# BRAINS.net
KiCad netlist of a schematic drawn in Altium Designer
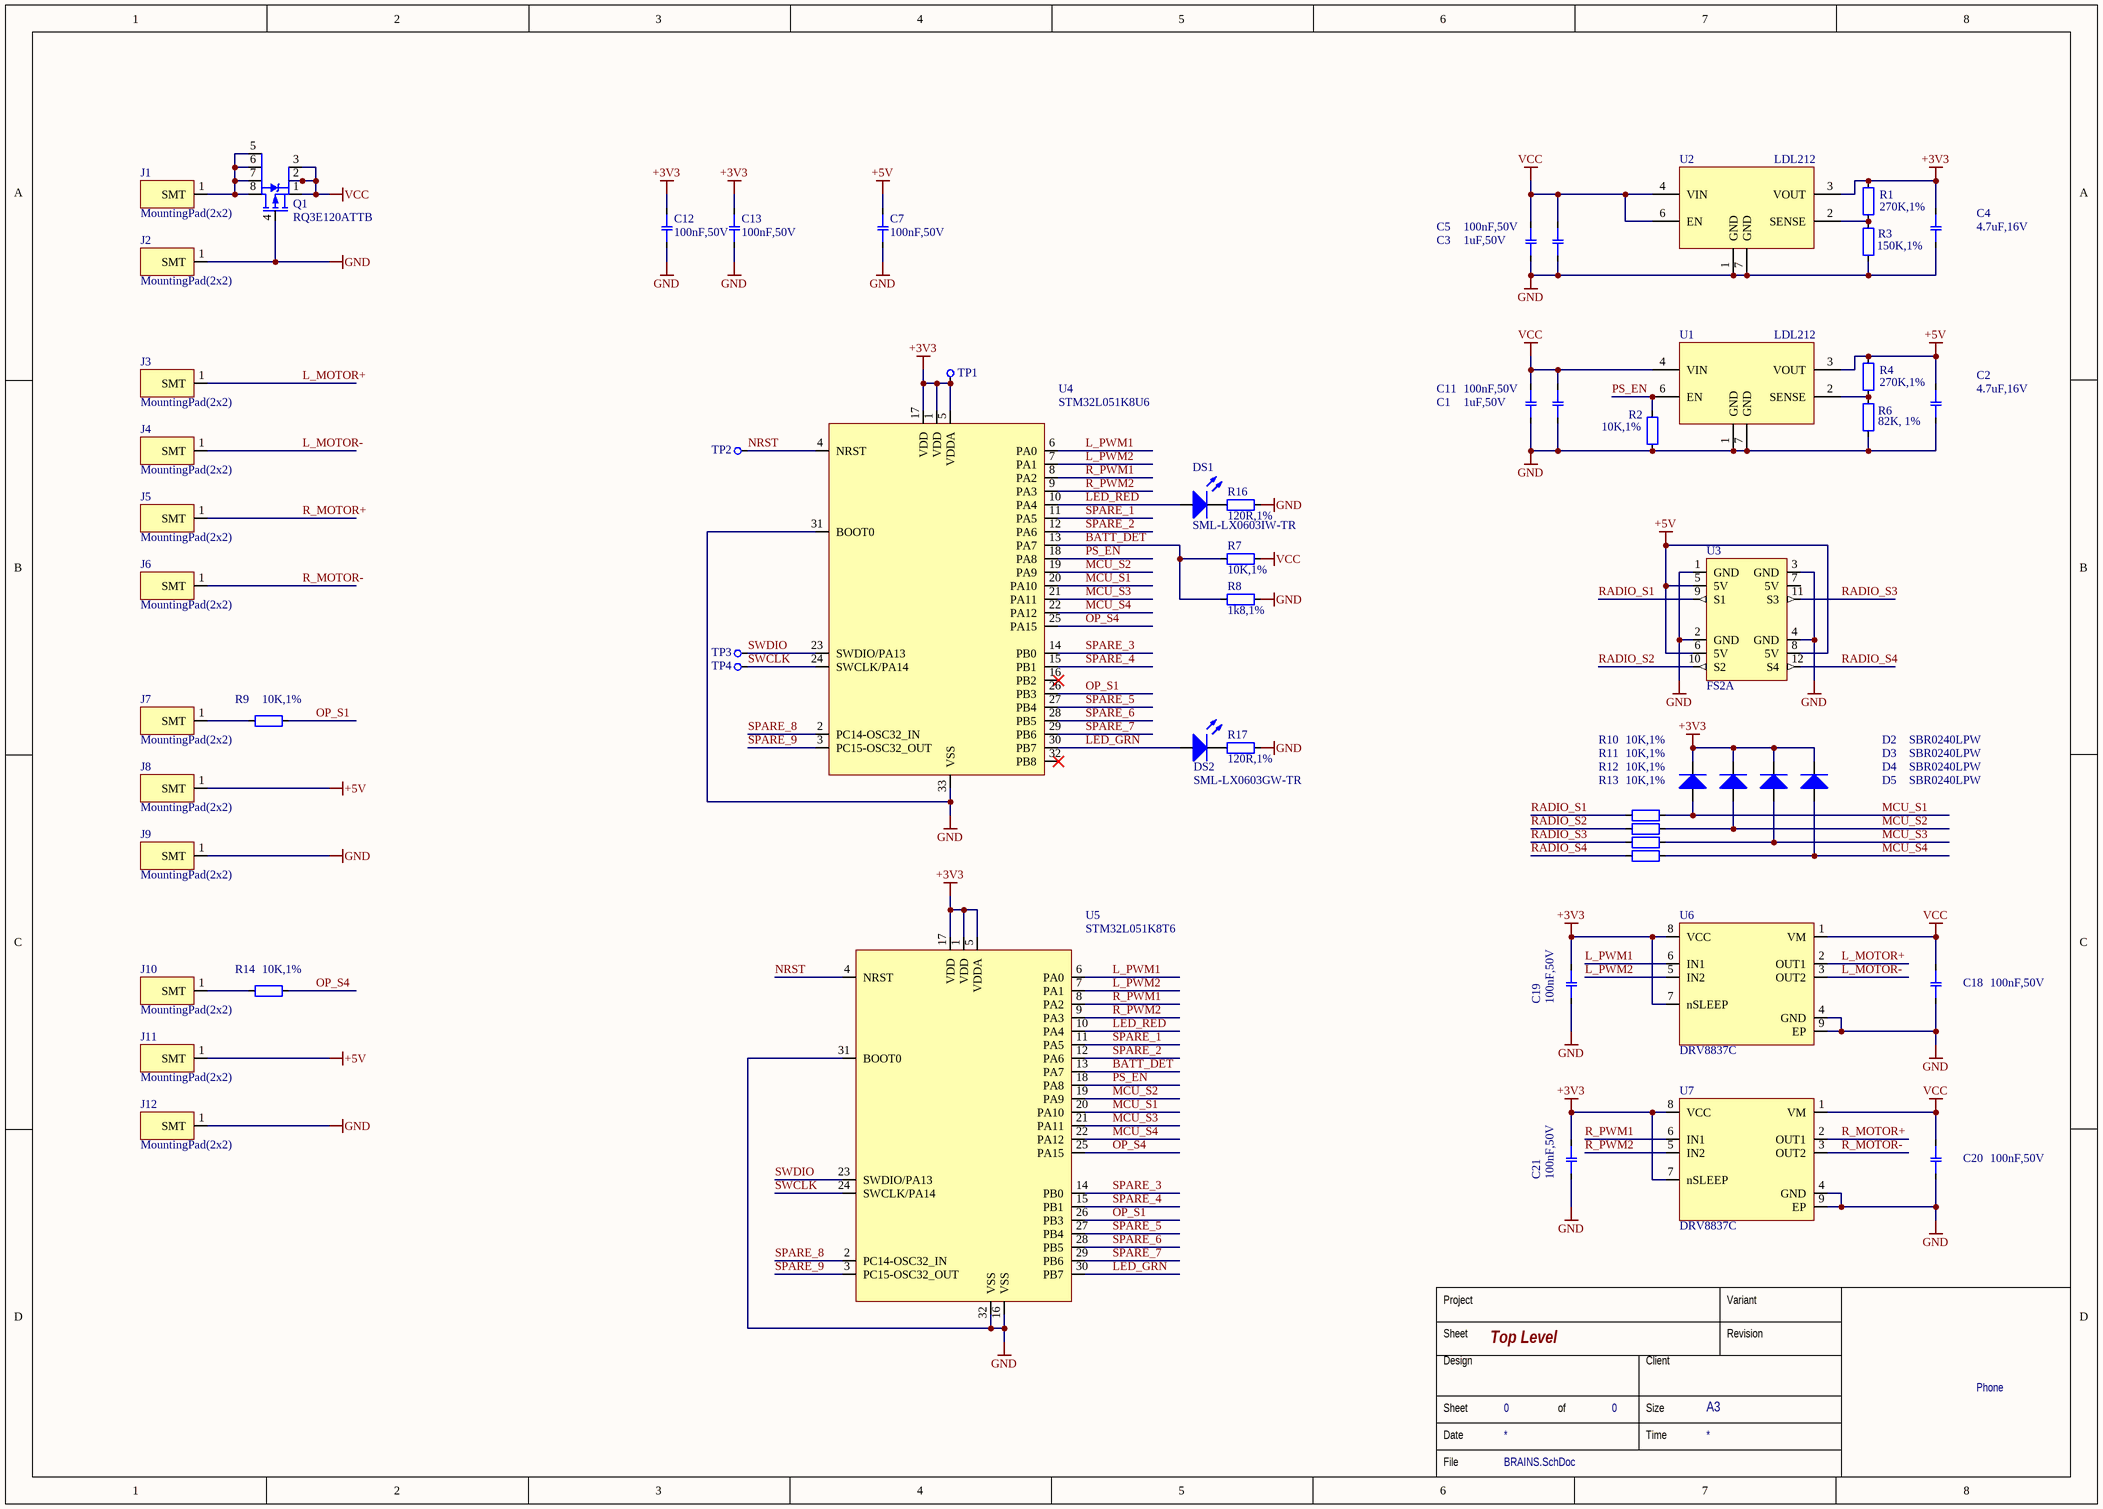
[diagram p0: BRAINS.SchDoc]

(export (version "E")
  (design (tool "Eeschema 10.0.6"))
  (components
    (comp (ref "C1")
      (value "1uF,50V")
      (footprint "CAPC1005X05N_0402")
      (description "CAP CER 1UF 50V X5R 0402")
      (fields (field (name "MANUFACTURER") "Taiyo Yuden") (field (name "TOLERANCE") "20%"))
      (libsource (lib "library") (part "CAP-NP_1"))
    )
    (comp (ref "C2")
      (value "4.7uF,16V")
      (footprint "CAPC1005X05N_0402")
      (description "CAP CER 4.7UF 16V X5R 0402")
      (fields (field (name "MANUFACTURER") "AVX Corporation") (field (name "TOLERANCE") "20%"))
      (libsource (lib "library") (part "CAP-NP_1"))
    )
    (comp (ref "C3")
      (value "1uF,50V")
      (footprint "CAPC1005X05N_0402")
      (description "CAP CER 1UF 50V X5R 0402")
      (fields (field (name "MANUFACTURER") "Taiyo Yuden") (field (name "TOLERANCE") "20%"))
      (libsource (lib "library") (part "CAP-NP_1"))
    )
    (comp (ref "C4")
      (value "4.7uF,16V")
      (footprint "CAPC1005X05N_0402")
      (description "CAP CER 4.7UF 16V X5R 0402")
      (fields (field (name "MANUFACTURER") "AVX Corporation") (field (name "TOLERANCE") "20%"))
      (libsource (lib "library") (part "CAP-NP_1"))
    )
    (comp (ref "C5")
      (value "100nF,50V")
      (footprint "CAPC1005X05N_0402")
      (description "CAP CER 100nF 50V X7R 0402")
      (fields (field (name "MANUFACTURER") "Taiyo Yuden") (field (name "TOLERANCE") "10%"))
      (libsource (lib "library") (part "CAP-NP_1"))
    )
    (comp (ref "C7")
      (value "100nF,50V")
      (footprint "CAPC1005X05N_0402")
      (description "CAP CER 100nF 50V X7R 0402")
      (fields (field (name "MANUFACTURER") "Taiyo Yuden") (field (name "TOLERANCE") "10%"))
      (libsource (lib "library") (part "CAP-NP_1"))
    )
    (comp (ref "C11")
      (value "100nF,50V")
      (footprint "CAPC1005X05N_0402")
      (description "CAP CER 100nF 50V X7R 0402")
      (fields (field (name "MANUFACTURER") "Taiyo Yuden") (field (name "TOLERANCE") "10%"))
      (libsource (lib "library") (part "CAP-NP_1"))
    )
    (comp (ref "C12")
      (value "100nF,50V")
      (footprint "CAPC1005X05N_0402")
      (description "CAP CER 100nF 50V X7R 0402")
      (fields (field (name "MANUFACTURER") "Taiyo Yuden") (field (name "TOLERANCE") "10%"))
      (libsource (lib "library") (part "CAP-NP_1"))
    )
    (comp (ref "C13")
      (value "100nF,50V")
      (footprint "CAPC1005X05N_0402")
      (description "CAP CER 100nF 50V X7R 0402")
      (fields (field (name "MANUFACTURER") "Taiyo Yuden") (field (name "TOLERANCE") "10%"))
      (libsource (lib "library") (part "CAP-NP_1"))
    )
    (comp (ref "C18")
      (value "100nF,50V")
      (footprint "CAPC1005X05N_0402")
      (description "CAP CER 100nF 50V X7R 0402")
      (fields (field (name "MANUFACTURER") "Taiyo Yuden") (field (name "TOLERANCE") "10%"))
      (libsource (lib "library") (part "CAP-NP_1"))
    )
    (comp (ref "C19")
      (value "100nF,50V")
      (footprint "CAPC1005X05N_0402")
      (description "CAP CER 100nF 50V X7R 0402")
      (fields (field (name "MANUFACTURER") "Taiyo Yuden") (field (name "TOLERANCE") "10%"))
      (libsource (lib "library") (part "CAP-NP_1"))
    )
    (comp (ref "C20")
      (value "100nF,50V")
      (footprint "CAPC1005X05N_0402")
      (description "CAP CER 100nF 50V X7R 0402")
      (fields (field (name "MANUFACTURER") "Taiyo Yuden") (field (name "TOLERANCE") "10%"))
      (libsource (lib "library") (part "CAP-NP_1"))
    )
    (comp (ref "C21")
      (value "100nF,50V")
      (footprint "CAPC1005X05N_0402")
      (description "CAP CER 100nF 50V X7R 0402")
      (fields (field (name "MANUFACTURER") "Taiyo Yuden") (field (name "TOLERANCE") "10%"))
      (libsource (lib "library") (part "CAP-NP_1"))
    )
    (comp (ref "D2")
      (value "SBR0240LPW")
      (footprint "TVS0402")
      (description "SBR DIODE X1-DFN1006-2/SWP")
      (fields
        (field (name "MANUFACTURER") "Diodes Incorporated")
        (field (name "MANUFACTURER PART NUMBER") "SBR0240LPW-7B")
      )
      (libsource (lib "library") (part "DIODE_1"))
    )
    (comp (ref "D3")
      (value "SBR0240LPW")
      (footprint "TVS0402")
      (description "SBR DIODE X1-DFN1006-2/SWP")
      (fields
        (field (name "MANUFACTURER") "Diodes Incorporated")
        (field (name "MANUFACTURER PART NUMBER") "SBR0240LPW-7B")
      )
      (libsource (lib "library") (part "DIODE_1"))
    )
    (comp (ref "D4")
      (value "SBR0240LPW")
      (footprint "TVS0402")
      (description "SBR DIODE X1-DFN1006-2/SWP")
      (fields
        (field (name "MANUFACTURER") "Diodes Incorporated")
        (field (name "MANUFACTURER PART NUMBER") "SBR0240LPW-7B")
      )
      (libsource (lib "library") (part "DIODE_1"))
    )
    (comp (ref "D5")
      (value "SBR0240LPW")
      (footprint "TVS0402")
      (description "SBR DIODE X1-DFN1006-2/SWP")
      (fields
        (field (name "MANUFACTURER") "Diodes Incorporated")
        (field (name "MANUFACTURER PART NUMBER") "SBR0240LPW-7B")
      )
      (libsource (lib "library") (part "DIODE_1"))
    )
    (comp (ref "DS1")
      (value "SML-LX0603IW-TR")
      (footprint "LED_SML-LX0603")
      (description "LED 635NM RED DIFF 0603 SMD")
      (fields (field (name "MANUFACTURER") "Lumex Opto/Components Inc"))
      (libsource (lib "library") (part "LED_1"))
    )
    (comp (ref "DS2")
      (value "SML-LX0603GW-TR")
      (footprint "LED_SML-LX0603")
      (description "LED 565NM GRN DIFF 0603 SMD")
      (fields (field (name "MANUFACTURER") "Lumex Opto/Components Inc"))
      (libsource (lib "library") (part "LED_1"))
    )
    (comp (ref "J1")
      (value "MountingPad(2x2)")
      (footprint "MountingPad(2x2)")
      (libsource (lib "") (part "MountingPad(2x2)_1"))
    )
    (comp (ref "J2")
      (value "MountingPad(2x2)")
      (footprint "MountingPad(2x2)")
      (libsource (lib "") (part "MountingPad(2x2)_1"))
    )
    (comp (ref "J3")
      (value "MountingPad(2x2)")
      (footprint "MountingPad(2x2)")
      (libsource (lib "Schlib1") (part "MountingPad(2x2)"))
    )
    (comp (ref "J4")
      (value "MountingPad(2x2)")
      (footprint "MountingPad(2x2)")
      (libsource (lib "Schlib1") (part "MountingPad(2x2)"))
    )
    (comp (ref "J5")
      (value "MountingPad(2x2)")
      (footprint "MountingPad(2x2)")
      (libsource (lib "Schlib1") (part "MountingPad(2x2)"))
    )
    (comp (ref "J6")
      (value "MountingPad(2x2)")
      (footprint "MountingPad(2x2)")
      (libsource (lib "Schlib1") (part "MountingPad(2x2)"))
    )
    (comp (ref "J7")
      (value "MountingPad(2x2)")
      (footprint "MountingPad(2x2)")
      (libsource (lib "Schlib1") (part "MountingPad(2x2)"))
    )
    (comp (ref "J8")
      (value "MountingPad(2x2)")
      (footprint "MountingPad(2x2)")
      (libsource (lib "Schlib1") (part "MountingPad(2x2)"))
    )
    (comp (ref "J9")
      (value "MountingPad(2x2)")
      (footprint "MountingPad(2x2)")
      (libsource (lib "Schlib1") (part "MountingPad(2x2)"))
    )
    (comp (ref "J10")
      (value "MountingPad(2x2)")
      (footprint "MountingPad(2x2)")
      (libsource (lib "Schlib1") (part "MountingPad(2x2)"))
    )
    (comp (ref "J11")
      (value "MountingPad(2x2)")
      (footprint "MountingPad(2x2)")
      (libsource (lib "Schlib1") (part "MountingPad(2x2)"))
    )
    (comp (ref "J12")
      (value "MountingPad(2x2)")
      (footprint "MountingPad(2x2)")
      (libsource (lib "Schlib1") (part "MountingPad(2x2)"))
    )
    (comp (ref "Q1")
      (value "RQ3E120ATTB")
      (footprint "ROHM-HSMT8")
      (description "MOSFET P-CH 30V 12A 8HSMT")
      (fields (field (name "MANUFACTURER") "Rohm Semiconductor"))
      (libsource (lib "library") (part "MOSFET-P_5"))
    )
    (comp (ref "R1")
      (value "270K,1%")
      (footprint "RESC1005X04N_0402")
      (description "RES SMD 270K OHM 1% 1/16W 0402")
      (fields (field (name "MANUFACTURER") "Yageo") (field (name "POWER") "0.063W"))
      (libsource (lib "library") (part "RESISTOR_1"))
    )
    (comp (ref "R2")
      (value "10K,1%")
      (footprint "RESC1005X04N_0402")
      (description "RES 10K OHM 1/16W 1% 0402 SMD")
      (fields (field (name "MANUFACTURER") "Yageo") (field (name "POWER") "0.0625W"))
      (libsource (lib "library") (part "RESISTOR_1"))
    )
    (comp (ref "R3")
      (value "150K,1%")
      (footprint "RESC1005X04N_0402")
      (description "RES SMD 150K OHM 1% 1/16W 0402")
      (fields (field (name "MANUFACTURER") "Yageo") (field (name "POWER") "0.063W"))
      (libsource (lib "library") (part "RESISTOR_1"))
    )
    (comp (ref "R4")
      (value "270K,1%")
      (footprint "RESC1005X04N_0402")
      (description "RES SMD 270K OHM 1% 1/16W 0402")
      (fields (field (name "MANUFACTURER") "Yageo") (field (name "POWER") "0.063W"))
      (libsource (lib "library") (part "RESISTOR_1"))
    )
    (comp (ref "R6")
      (value "82K, 1%")
      (footprint "RESC1005X04N_0402")
      (description "RES SMD 82K OHM 1% 1/16W 0402")
      (fields (field (name "MANUFACTURER") "YAGEO") (field (name "POWER") "0.063W"))
      (libsource (lib "library") (part "RESISTOR_1"))
    )
    (comp (ref "R7")
      (value "10K,1%")
      (footprint "RESC1005X04N_0402")
      (description "RES 10K OHM 1/16W 1% 0402 SMD")
      (fields (field (name "MANUFACTURER") "Yageo") (field (name "POWER") "0.0625W"))
      (libsource (lib "") (part "RESISTOR_1_2"))
    )
    (comp (ref "R8")
      (value "1k8,1%")
      (footprint "RESC1005X04N_0402")
      (description "RES 1k8 0.0625W 1% 0402 SMD")
      (fields (field (name "MANUFACTURER") "Vishay Dale") (field (name "POWER") "0.0625W"))
      (libsource (lib "") (part "RESISTOR_1_2"))
    )
    (comp (ref "R9")
      (value "10K,1%")
      (footprint "RESC1005X04N_0402")
      (description "RES 10K OHM 1/16W 1% 0402 SMD")
      (fields (field (name "MANUFACTURER") "Yageo") (field (name "POWER") "0.0625W"))
      (libsource (lib "") (part "RESISTOR_1_1"))
    )
    (comp (ref "R10")
      (value "10K,1%")
      (footprint "RESC1005X04N_0402")
      (description "RES 10K OHM 1/16W 1% 0402 SMD")
      (fields (field (name "MANUFACTURER") "Yageo") (field (name "POWER") "0.0625W"))
      (libsource (lib "") (part "RESISTOR_1_1"))
    )
    (comp (ref "R11")
      (value "10K,1%")
      (footprint "RESC1005X04N_0402")
      (description "RES 10K OHM 1/16W 1% 0402 SMD")
      (fields (field (name "MANUFACTURER") "Yageo") (field (name "POWER") "0.0625W"))
      (libsource (lib "") (part "RESISTOR_1_1"))
    )
    (comp (ref "R12")
      (value "10K,1%")
      (footprint "RESC1005X04N_0402")
      (description "RES 10K OHM 1/16W 1% 0402 SMD")
      (fields (field (name "MANUFACTURER") "Yageo") (field (name "POWER") "0.0625W"))
      (libsource (lib "") (part "RESISTOR_1_1"))
    )
    (comp (ref "R13")
      (value "10K,1%")
      (footprint "RESC1005X04N_0402")
      (description "RES 10K OHM 1/16W 1% 0402 SMD")
      (fields (field (name "MANUFACTURER") "Yageo") (field (name "POWER") "0.0625W"))
      (libsource (lib "") (part "RESISTOR_1_1"))
    )
    (comp (ref "R14")
      (value "10K,1%")
      (footprint "RESC1005X04N_0402")
      (description "RES 10K OHM 1/16W 1% 0402 SMD")
      (fields (field (name "MANUFACTURER") "Yageo") (field (name "POWER") "0.0625W"))
      (libsource (lib "") (part "RESISTOR_1_1"))
    )
    (comp (ref "R16")
      (value "120R,1%")
      (footprint "RESC1005X04N_0402")
      (description "RES 120 OHM 1/16W 0402 SMD")
      (fields (field (name "MANUFACTURER") "Yageo") (field (name "POWER") "0.0625W"))
      (libsource (lib "") (part "RESISTOR_1_2"))
    )
    (comp (ref "R17")
      (value "120R,1%")
      (footprint "RESC1005X04N_0402")
      (description "RES 120 OHM 1/16W 0402 SMD")
      (fields (field (name "MANUFACTURER") "Yageo") (field (name "POWER") "0.0625W"))
      (libsource (lib "") (part "RESISTOR_1_2"))
    )
    (comp (ref "TP1")
      (value "TP_SMT")
      (footprint "TP_050")
      (description "Test Point - SMT")
      (libsource (lib "library") (part "TP_1"))
    )
    (comp (ref "TP2")
      (value "TP_SMT")
      (footprint "TP_050")
      (description "Test Point - SMT")
      (libsource (lib "library") (part "TP_1"))
    )
    (comp (ref "TP3")
      (value "TP_SMT")
      (footprint "TP_050")
      (description "Test Point - SMT")
      (libsource (lib "library") (part "TP_1"))
    )
    (comp (ref "TP4")
      (value "TP_SMT")
      (footprint "TP_050")
      (description "Test Point - SMT")
      (libsource (lib "library") (part "TP_1"))
    )
    (comp (ref "U1")
      (value "LDL212")
      (footprint "DFN65P300X300X80-8N_PWSON6")
      (description "IC REG LINEAR 5V 1.2A 6DFN")
      (fields
        (field (name "MANUFACTURER") "STMicroelectronics")
        (field (name "MANUFACTURER PART NUMBER") "LDL212PU50R")
      )
      (libsource (lib "library") (part "LDL212PU50R"))
    )
    (comp (ref "U2")
      (value "LDL212")
      (footprint "DFN65P300X300X80-8N_PWSON6")
      (description "IC REG LINEAR 5V 1.2A 6DFN")
      (fields
        (field (name "MANUFACTURER") "STMicroelectronics")
        (field (name "MANUFACTURER PART NUMBER") "LDL212PU50R")
      )
      (libsource (lib "library") (part "LDL212PU50R"))
    )
    (comp (ref "U3") (value "FS2A") (footprint "FS2A") (libsource (lib "Schlib1") (part "FS2A")))
    (comp (ref "U4")
      (value "STM32L051K8U6")
      (footprint "QFN50P500X500X100-32N_32QFN_2")
      (description "IC MCU 32BIT 64KB FLASH 32UFQFPN")
      (fields (field (name "MANUFACTURER") "STMicroelectronics"))
      (libsource (lib "library") (part "STM32L051x6/8U"))
    )
    (comp (ref "U5")
      (value "STM32L051K8T6")
      (footprint "LQFP32")
      (description "32 Bit Mcirocontroler")
      (fields (field (name "MANUFACTURER") "ST Microelectronics"))
      (libsource (lib "library") (part "STM32L051x6/8"))
    )
    (comp (ref "U6")
      (value "DRV8837C")
      (footprint "DFN50P200X200X80-8N")
      (description "IC HALF-BRIDGE DRVR PWM 8WSON")
      (fields
        (field (name "MANUFACTURER") "Texas Instruments")
        (field (name "MANUFACTURER PART NUMBER") "DRV8837CDSGR")
      )
      (libsource (lib "library") (part "DRV8837C"))
    )
    (comp (ref "U7")
      (value "DRV8837C")
      (footprint "DFN50P200X200X80-8N")
      (description "IC HALF-BRIDGE DRVR PWM 8WSON")
      (fields
        (field (name "MANUFACTURER") "Texas Instruments")
        (field (name "MANUFACTURER PART NUMBER") "DRV8837CDSGR")
      )
      (libsource (lib "library") (part "DRV8837C"))
    )
  )
  (nets
    (net (code "1") (name "+3V3") (class "Default")
      (node (ref "C12") (pin "2") (pinfunction "2_2") (pintype "passive"))
      (node (ref "C13") (pin "2") (pinfunction "2_2") (pintype "passive"))
      (node (ref "C19") (pin "2") (pinfunction "2_2") (pintype "passive"))
      (node (ref "C21") (pin "2") (pinfunction "2_2") (pintype "passive"))
      (node (ref "C4") (pin "2") (pinfunction "2_2") (pintype "passive"))
      (node (ref "D2") (pin "1") (pinfunction "C_1") (pintype "passive"))
      (node (ref "D3") (pin "1") (pinfunction "C_1") (pintype "passive"))
      (node (ref "D4") (pin "1") (pinfunction "C_1") (pintype "passive"))
      (node (ref "D5") (pin "1") (pinfunction "C_1") (pintype "passive"))
      (node (ref "R1") (pin "2") (pinfunction "2_2") (pintype "passive"))
      (node (ref "TP1") (pin "1") (pinfunction "1_1") (pintype "passive"))
      (node (ref "U2") (pin "3") (pinfunction "VOUT_3") (pintype "passive"))
      (node (ref "U4") (pin "1") (pinfunction "VDD_1") (pintype "passive"))
      (node (ref "U4") (pin "17") (pinfunction "VDD_17") (pintype "passive"))
      (node (ref "U4") (pin "5") (pinfunction "VDDA_5") (pintype "passive"))
      (node (ref "U5") (pin "1") (pinfunction "VDD_1") (pintype "passive"))
      (node (ref "U5") (pin "17") (pinfunction "VDD_17") (pintype "passive"))
      (node (ref "U5") (pin "5") (pinfunction "VDDA_5") (pintype "passive"))
      (node (ref "U6") (pin "7") (pinfunction "nSLEEP_7") (pintype "passive"))
      (node (ref "U6") (pin "8") (pinfunction "VCC_8") (pintype "passive"))
      (node (ref "U7") (pin "7") (pinfunction "nSLEEP_7") (pintype "passive"))
      (node (ref "U7") (pin "8") (pinfunction "VCC_8") (pintype "passive"))
    )
    (net (code "2") (name "+5V") (class "Default")
      (node (ref "C2") (pin "2") (pinfunction "2_2") (pintype "passive"))
      (node (ref "C7") (pin "2") (pinfunction "2_2") (pintype "passive"))
      (node (ref "J11") (pin "1") (pinfunction "SMT_1") (pintype "passive"))
      (node (ref "J8") (pin "1") (pinfunction "SMT_1") (pintype "passive"))
      (node (ref "R4") (pin "2") (pinfunction "2_2") (pintype "passive"))
      (node (ref "U1") (pin "3") (pinfunction "VOUT_3") (pintype "passive"))
      (node (ref "U3") (pin "5") (pinfunction "5V_5") (pintype "power_in"))
      (node (ref "U3") (pin "6") (pinfunction "5V_6") (pintype "power_in"))
      (node (ref "U3") (pin "8") (pinfunction "5V_8") (pintype "power_in"))
    )
    (net (code "3") (name "/BATT_DET") (class "Default")
      (node (ref "R7") (pin "2") (pinfunction "2_2") (pintype "passive"))
      (node (ref "R8") (pin "2") (pinfunction "2_2") (pintype "passive"))
      (node (ref "U4") (pin "13") (pinfunction "PA7_13") (pintype "passive"))
      (node (ref "U5") (pin "13") (pinfunction "PA7_13") (pintype "passive"))
    )
    (net (code "4") (name "/LED_GRN") (class "Default")
      (node (ref "DS2") (pin "2") (pinfunction "A_2") (pintype "passive"))
      (node (ref "U4") (pin "30") (pinfunction "PB7_30") (pintype "passive"))
      (node (ref "U5") (pin "30") (pinfunction "PB7_30") (pintype "passive"))
    )
    (net (code "5") (name "/LED_RED") (class "Default")
      (node (ref "DS1") (pin "2") (pinfunction "A_2") (pintype "passive"))
      (node (ref "U4") (pin "10") (pinfunction "PA4_10") (pintype "passive"))
      (node (ref "U5") (pin "10") (pinfunction "PA4_10") (pintype "passive"))
    )
    (net (code "6") (name "/L_MOTOR+") (class "Default")
      (node (ref "J3") (pin "1") (pinfunction "SMT_1") (pintype "passive"))
      (node (ref "U6") (pin "2") (pinfunction "OUT1_2") (pintype "passive"))
    )
    (net (code "7") (name "/L_MOTOR-") (class "Default")
      (node (ref "J4") (pin "1") (pinfunction "SMT_1") (pintype "passive"))
      (node (ref "U6") (pin "3") (pinfunction "OUT2_3") (pintype "passive"))
    )
    (net (code "8") (name "/L_PWM1") (class "Default")
      (node (ref "U4") (pin "6") (pinfunction "PA0_6") (pintype "passive"))
      (node (ref "U5") (pin "6") (pinfunction "PA0_6") (pintype "passive"))
      (node (ref "U6") (pin "6") (pinfunction "IN1_6") (pintype "passive"))
    )
    (net (code "9") (name "/L_PWM2") (class "Default")
      (node (ref "U4") (pin "7") (pinfunction "PA1_7") (pintype "passive"))
      (node (ref "U5") (pin "7") (pinfunction "PA1_7") (pintype "passive"))
      (node (ref "U6") (pin "5") (pinfunction "IN2_5") (pintype "passive"))
    )
    (net (code "10") (name "/MCU_S1") (class "Default")
      (node (ref "D5") (pin "2") (pinfunction "A_2") (pintype "passive"))
      (node (ref "R10") (pin "1") (pinfunction "1_1") (pintype "passive"))
      (node (ref "U4") (pin "20") (pinfunction "PA10_20") (pintype "passive"))
      (node (ref "U5") (pin "20") (pinfunction "PA10_20") (pintype "passive"))
    )
    (net (code "11") (name "/MCU_S2") (class "Default")
      (node (ref "D4") (pin "2") (pinfunction "A_2") (pintype "passive"))
      (node (ref "R11") (pin "1") (pinfunction "1_1") (pintype "passive"))
      (node (ref "U4") (pin "19") (pinfunction "PA9_19") (pintype "passive"))
      (node (ref "U5") (pin "19") (pinfunction "PA9_19") (pintype "passive"))
    )
    (net (code "12") (name "/MCU_S3") (class "Default")
      (node (ref "D3") (pin "2") (pinfunction "A_2") (pintype "passive"))
      (node (ref "R12") (pin "1") (pinfunction "1_1") (pintype "passive"))
      (node (ref "U4") (pin "21") (pinfunction "PA11_21") (pintype "passive"))
      (node (ref "U5") (pin "21") (pinfunction "PA11_21") (pintype "passive"))
    )
    (net (code "13") (name "/MCU_S4") (class "Default")
      (node (ref "D2") (pin "2") (pinfunction "A_2") (pintype "passive"))
      (node (ref "R13") (pin "1") (pinfunction "1_1") (pintype "passive"))
      (node (ref "U4") (pin "22") (pinfunction "PA12_22") (pintype "passive"))
      (node (ref "U5") (pin "22") (pinfunction "PA12_22") (pintype "passive"))
    )
    (net (code "14") (name "/NRST") (class "Default")
      (node (ref "TP2") (pin "1") (pinfunction "1_1") (pintype "passive"))
      (node (ref "U4") (pin "4") (pinfunction "NRST_4") (pintype "passive"))
      (node (ref "U5") (pin "4") (pinfunction "NRST_4") (pintype "passive"))
    )
    (net (code "15") (name "/OP_S1") (class "Default")
      (node (ref "R9") (pin "1") (pinfunction "1_1") (pintype "passive"))
      (node (ref "U4") (pin "26") (pinfunction "PB3_26") (pintype "passive"))
      (node (ref "U5") (pin "26") (pinfunction "PB3_26") (pintype "passive"))
    )
    (net (code "16") (name "/OP_S4") (class "Default")
      (node (ref "R14") (pin "1") (pinfunction "1_1") (pintype "passive"))
      (node (ref "U4") (pin "25") (pinfunction "PA15_25") (pintype "passive"))
      (node (ref "U5") (pin "25") (pinfunction "PA15_25") (pintype "passive"))
    )
    (net (code "17") (name "/PS_EN") (class "Default")
      (node (ref "R2") (pin "2") (pinfunction "2_2") (pintype "passive"))
      (node (ref "U1") (pin "6") (pinfunction "EN_6") (pintype "passive"))
      (node (ref "U4") (pin "18") (pinfunction "PA8_18") (pintype "passive"))
      (node (ref "U5") (pin "18") (pinfunction "PA8_18") (pintype "passive"))
    )
    (net (code "18") (name "/RADIO_S1") (class "Default")
      (node (ref "R10") (pin "2") (pinfunction "2_2") (pintype "passive"))
      (node (ref "U3") (pin "9") (pinfunction "S1_9") (pintype "output"))
    )
    (net (code "19") (name "/RADIO_S2") (class "Default")
      (node (ref "R11") (pin "2") (pinfunction "2_2") (pintype "passive"))
      (node (ref "U3") (pin "10") (pinfunction "S2_10") (pintype "output"))
    )
    (net (code "20") (name "/RADIO_S3") (class "Default")
      (node (ref "R12") (pin "2") (pinfunction "2_2") (pintype "passive"))
      (node (ref "U3") (pin "11") (pinfunction "S3_11") (pintype "output"))
    )
    (net (code "21") (name "/RADIO_S4") (class "Default")
      (node (ref "R13") (pin "2") (pinfunction "2_2") (pintype "passive"))
      (node (ref "U3") (pin "12") (pinfunction "S4_12") (pintype "output"))
    )
    (net (code "22") (name "/R_MOTOR+") (class "Default")
      (node (ref "J5") (pin "1") (pinfunction "SMT_1") (pintype "passive"))
      (node (ref "U7") (pin "2") (pinfunction "OUT1_2") (pintype "passive"))
    )
    (net (code "23") (name "/R_MOTOR-") (class "Default")
      (node (ref "J6") (pin "1") (pinfunction "SMT_1") (pintype "passive"))
      (node (ref "U7") (pin "3") (pinfunction "OUT2_3") (pintype "passive"))
    )
    (net (code "24") (name "/R_PWM1") (class "Default")
      (node (ref "U4") (pin "8") (pinfunction "PA2_8") (pintype "passive"))
      (node (ref "U5") (pin "8") (pinfunction "PA2_8") (pintype "passive"))
      (node (ref "U7") (pin "6") (pinfunction "IN1_6") (pintype "passive"))
    )
    (net (code "25") (name "/R_PWM2") (class "Default")
      (node (ref "U4") (pin "9") (pinfunction "PA3_9") (pintype "passive"))
      (node (ref "U5") (pin "9") (pinfunction "PA3_9") (pintype "passive"))
      (node (ref "U7") (pin "5") (pinfunction "IN2_5") (pintype "passive"))
    )
    (net (code "26") (name "/SPARE_1") (class "Default")
      (node (ref "U4") (pin "11") (pinfunction "PA5_11") (pintype "passive"))
      (node (ref "U5") (pin "11") (pinfunction "PA5_11") (pintype "passive"))
    )
    (net (code "27") (name "/SPARE_2") (class "Default")
      (node (ref "U4") (pin "12") (pinfunction "PA6_12") (pintype "passive"))
      (node (ref "U5") (pin "12") (pinfunction "PA6_12") (pintype "passive"))
    )
    (net (code "28") (name "/SPARE_3") (class "Default")
      (node (ref "U4") (pin "14") (pinfunction "PB0_14") (pintype "passive"))
      (node (ref "U5") (pin "14") (pinfunction "PB0_14") (pintype "passive"))
    )
    (net (code "29") (name "/SPARE_4") (class "Default")
      (node (ref "U4") (pin "15") (pinfunction "PB1_15") (pintype "passive"))
      (node (ref "U5") (pin "15") (pinfunction "PB1_15") (pintype "passive"))
    )
    (net (code "30") (name "/SPARE_5") (class "Default")
      (node (ref "U4") (pin "27") (pinfunction "PB4_27") (pintype "passive"))
      (node (ref "U5") (pin "27") (pinfunction "PB4_27") (pintype "passive"))
    )
    (net (code "31") (name "/SPARE_6") (class "Default")
      (node (ref "U4") (pin "28") (pinfunction "PB5_28") (pintype "passive"))
      (node (ref "U5") (pin "28") (pinfunction "PB5_28") (pintype "passive"))
    )
    (net (code "32") (name "/SPARE_7") (class "Default")
      (node (ref "U4") (pin "29") (pinfunction "PB6_29") (pintype "passive"))
      (node (ref "U5") (pin "29") (pinfunction "PB6_29") (pintype "passive"))
    )
    (net (code "33") (name "/SPARE_8") (class "Default")
      (node (ref "U4") (pin "2") (pinfunction "PC14-OSC32_IN_2") (pintype "passive"))
      (node (ref "U5") (pin "2") (pinfunction "PC14-OSC32_IN_2") (pintype "passive"))
    )
    (net (code "34") (name "/SPARE_9") (class "Default")
      (node (ref "U4") (pin "3") (pinfunction "PC15-OSC32_OUT_3") (pintype "passive"))
      (node (ref "U5") (pin "3") (pinfunction "PC15-OSC32_OUT_3") (pintype "passive"))
    )
    (net (code "35") (name "/SWCLK") (class "Default")
      (node (ref "TP4") (pin "1") (pinfunction "1_1") (pintype "passive"))
      (node (ref "U4") (pin "24") (pinfunction "SWCLK/PA14_24") (pintype "passive"))
      (node (ref "U5") (pin "24") (pinfunction "SWCLK/PA14_24") (pintype "passive"))
    )
    (net (code "36") (name "/SWDIO") (class "Default")
      (node (ref "TP3") (pin "1") (pinfunction "1_1") (pintype "passive"))
      (node (ref "U4") (pin "23") (pinfunction "SWDIO/PA13_23") (pintype "passive"))
      (node (ref "U5") (pin "23") (pinfunction "SWDIO/PA13_23") (pintype "passive"))
    )
    (net (code "37") (name "GND") (class "Default")
      (node (ref "C1") (pin "1") (pinfunction "1_1") (pintype "passive"))
      (node (ref "C11") (pin "1") (pinfunction "1_1") (pintype "passive"))
      (node (ref "C12") (pin "1") (pinfunction "1_1") (pintype "passive"))
      (node (ref "C13") (pin "1") (pinfunction "1_1") (pintype "passive"))
      (node (ref "C18") (pin "1") (pinfunction "1_1") (pintype "passive"))
      (node (ref "C19") (pin "1") (pinfunction "1_1") (pintype "passive"))
      (node (ref "C2") (pin "1") (pinfunction "1_1") (pintype "passive"))
      (node (ref "C20") (pin "1") (pinfunction "1_1") (pintype "passive"))
      (node (ref "C21") (pin "1") (pinfunction "1_1") (pintype "passive"))
      (node (ref "C3") (pin "1") (pinfunction "1_1") (pintype "passive"))
      (node (ref "C4") (pin "1") (pinfunction "1_1") (pintype "passive"))
      (node (ref "C5") (pin "1") (pinfunction "1_1") (pintype "passive"))
      (node (ref "C7") (pin "1") (pinfunction "1_1") (pintype "passive"))
      (node (ref "J12") (pin "1") (pinfunction "SMT_1") (pintype "passive"))
      (node (ref "J2") (pin "1") (pinfunction "SMT_1") (pintype "passive"))
      (node (ref "J9") (pin "1") (pinfunction "SMT_1") (pintype "passive"))
      (node (ref "Q1") (pin "4") (pinfunction "G_4") (pintype "passive"))
      (node (ref "R16") (pin "1") (pinfunction "1_1") (pintype "passive"))
      (node (ref "R17") (pin "1") (pinfunction "1_1") (pintype "passive"))
      (node (ref "R2") (pin "1") (pinfunction "1_1") (pintype "passive"))
      (node (ref "R3") (pin "1") (pinfunction "1_1") (pintype "passive"))
      (node (ref "R6") (pin "1") (pinfunction "1_1") (pintype "passive"))
      (node (ref "R8") (pin "1") (pinfunction "1_1") (pintype "passive"))
      (node (ref "U1") (pin "1") (pinfunction "GND_1") (pintype "passive"))
      (node (ref "U1") (pin "7") (pinfunction "GND_7") (pintype "passive"))
      (node (ref "U2") (pin "1") (pinfunction "GND_1") (pintype "passive"))
      (node (ref "U2") (pin "7") (pinfunction "GND_7") (pintype "passive"))
      (node (ref "U3") (pin "1") (pinfunction "GND_1") (pintype "power_in"))
      (node (ref "U3") (pin "2") (pinfunction "GND_2") (pintype "power_in"))
      (node (ref "U3") (pin "3") (pinfunction "GND_3") (pintype "power_in"))
      (node (ref "U3") (pin "4") (pinfunction "GND_4") (pintype "power_in"))
      (node (ref "U4") (pin "31") (pinfunction "BOOT0_31") (pintype "passive"))
      (node (ref "U4") (pin "33") (pinfunction "VSS_33") (pintype "passive"))
      (node (ref "U5") (pin "16") (pinfunction "VSS_16") (pintype "passive"))
      (node (ref "U5") (pin "31") (pinfunction "BOOT0_31") (pintype "passive"))
      (node (ref "U5") (pin "32") (pinfunction "VSS_32") (pintype "passive"))
      (node (ref "U6") (pin "4") (pinfunction "GND_4") (pintype "passive"))
      (node (ref "U6") (pin "9") (pinfunction "EP_9") (pintype "passive"))
      (node (ref "U7") (pin "4") (pinfunction "GND_4") (pintype "passive"))
      (node (ref "U7") (pin "9") (pinfunction "EP_9") (pintype "passive"))
    )
    (net (code "38") (name "Net-(DS1-C)") (class "Default")
      (node (ref "DS1") (pin "1") (pinfunction "C_1") (pintype "passive"))
      (node (ref "R16") (pin "2") (pinfunction "2_2") (pintype "passive"))
    )
    (net (code "39") (name "Net-(DS2-C)") (class "Default")
      (node (ref "DS2") (pin "1") (pinfunction "C_1") (pintype "passive"))
      (node (ref "R17") (pin "2") (pinfunction "2_2") (pintype "passive"))
    )
    (net (code "40") (name "Net-(J1-SMT)") (class "Default")
      (node (ref "J1") (pin "1") (pinfunction "SMT_1") (pintype "passive"))
      (node (ref "Q1") (pin "5") (pinfunction "D_5") (pintype "passive"))
      (node (ref "Q1") (pin "6") (pinfunction "D_6") (pintype "passive"))
      (node (ref "Q1") (pin "7") (pinfunction "D_7") (pintype "passive"))
      (node (ref "Q1") (pin "8") (pinfunction "D_8") (pintype "passive"))
    )
    (net (code "41") (name "Net-(J7-SMT)") (class "Default")
      (node (ref "J7") (pin "1") (pinfunction "SMT_1") (pintype "passive"))
      (node (ref "R9") (pin "2") (pinfunction "2_2") (pintype "passive"))
    )
    (net (code "42") (name "Net-(J10-SMT)") (class "Default")
      (node (ref "J10") (pin "1") (pinfunction "SMT_1") (pintype "passive"))
      (node (ref "R14") (pin "2") (pinfunction "2_2") (pintype "passive"))
    )
    (net (code "43") (name "Net-(U1-SENSE)") (class "Default")
      (node (ref "R4") (pin "1") (pinfunction "1_1") (pintype "passive"))
      (node (ref "R6") (pin "2") (pinfunction "2_2") (pintype "passive"))
      (node (ref "U1") (pin "2") (pinfunction "SENSE_2") (pintype "passive"))
    )
    (net (code "44") (name "Net-(U2-SENSE)") (class "Default")
      (node (ref "R1") (pin "1") (pinfunction "1_1") (pintype "passive"))
      (node (ref "R3") (pin "2") (pinfunction "2_2") (pintype "passive"))
      (node (ref "U2") (pin "2") (pinfunction "SENSE_2") (pintype "passive"))
    )
    (net (code "45") (name "VCC") (class "Default")
      (node (ref "C1") (pin "2") (pinfunction "2_2") (pintype "passive"))
      (node (ref "C11") (pin "2") (pinfunction "2_2") (pintype "passive"))
      (node (ref "C18") (pin "2") (pinfunction "2_2") (pintype "passive"))
      (node (ref "C20") (pin "2") (pinfunction "2_2") (pintype "passive"))
      (node (ref "C3") (pin "2") (pinfunction "2_2") (pintype "passive"))
      (node (ref "C5") (pin "2") (pinfunction "2_2") (pintype "passive"))
      (node (ref "Q1") (pin "1") (pinfunction "S_1") (pintype "passive"))
      (node (ref "Q1") (pin "2") (pinfunction "S_2") (pintype "passive"))
      (node (ref "Q1") (pin "3") (pinfunction "S_3") (pintype "passive"))
      (node (ref "R7") (pin "1") (pinfunction "1_1") (pintype "passive"))
      (node (ref "U1") (pin "4") (pinfunction "VIN_4") (pintype "passive"))
      (node (ref "U2") (pin "4") (pinfunction "VIN_4") (pintype "passive"))
      (node (ref "U2") (pin "6") (pinfunction "EN_6") (pintype "passive"))
      (node (ref "U6") (pin "1") (pinfunction "VM_1") (pintype "passive"))
      (node (ref "U7") (pin "1") (pinfunction "VM_1") (pintype "passive"))
    )
    (net (code "46") (name "unconnected-(U3-5V-Pad7)") (class "Default")
      (node (ref "U3") (pin "7") (pinfunction "5V_7") (pintype "power_in"))
    )
    (net (code "47") (name "unconnected-(U4-PB2-Pad16)") (class "Default")
      (node (ref "U4") (pin "16") (pinfunction "PB2_16") (pintype "passive+no_connect"))
    )
    (net (code "48") (name "unconnected-(U4-PB8-Pad32)") (class "Default")
      (node (ref "U4") (pin "32") (pinfunction "PB8_32") (pintype "passive+no_connect"))
    )
  )
)
